# MODULIQ_TDC.net
KiCad netlist of a schematic drawn in Altium Designer
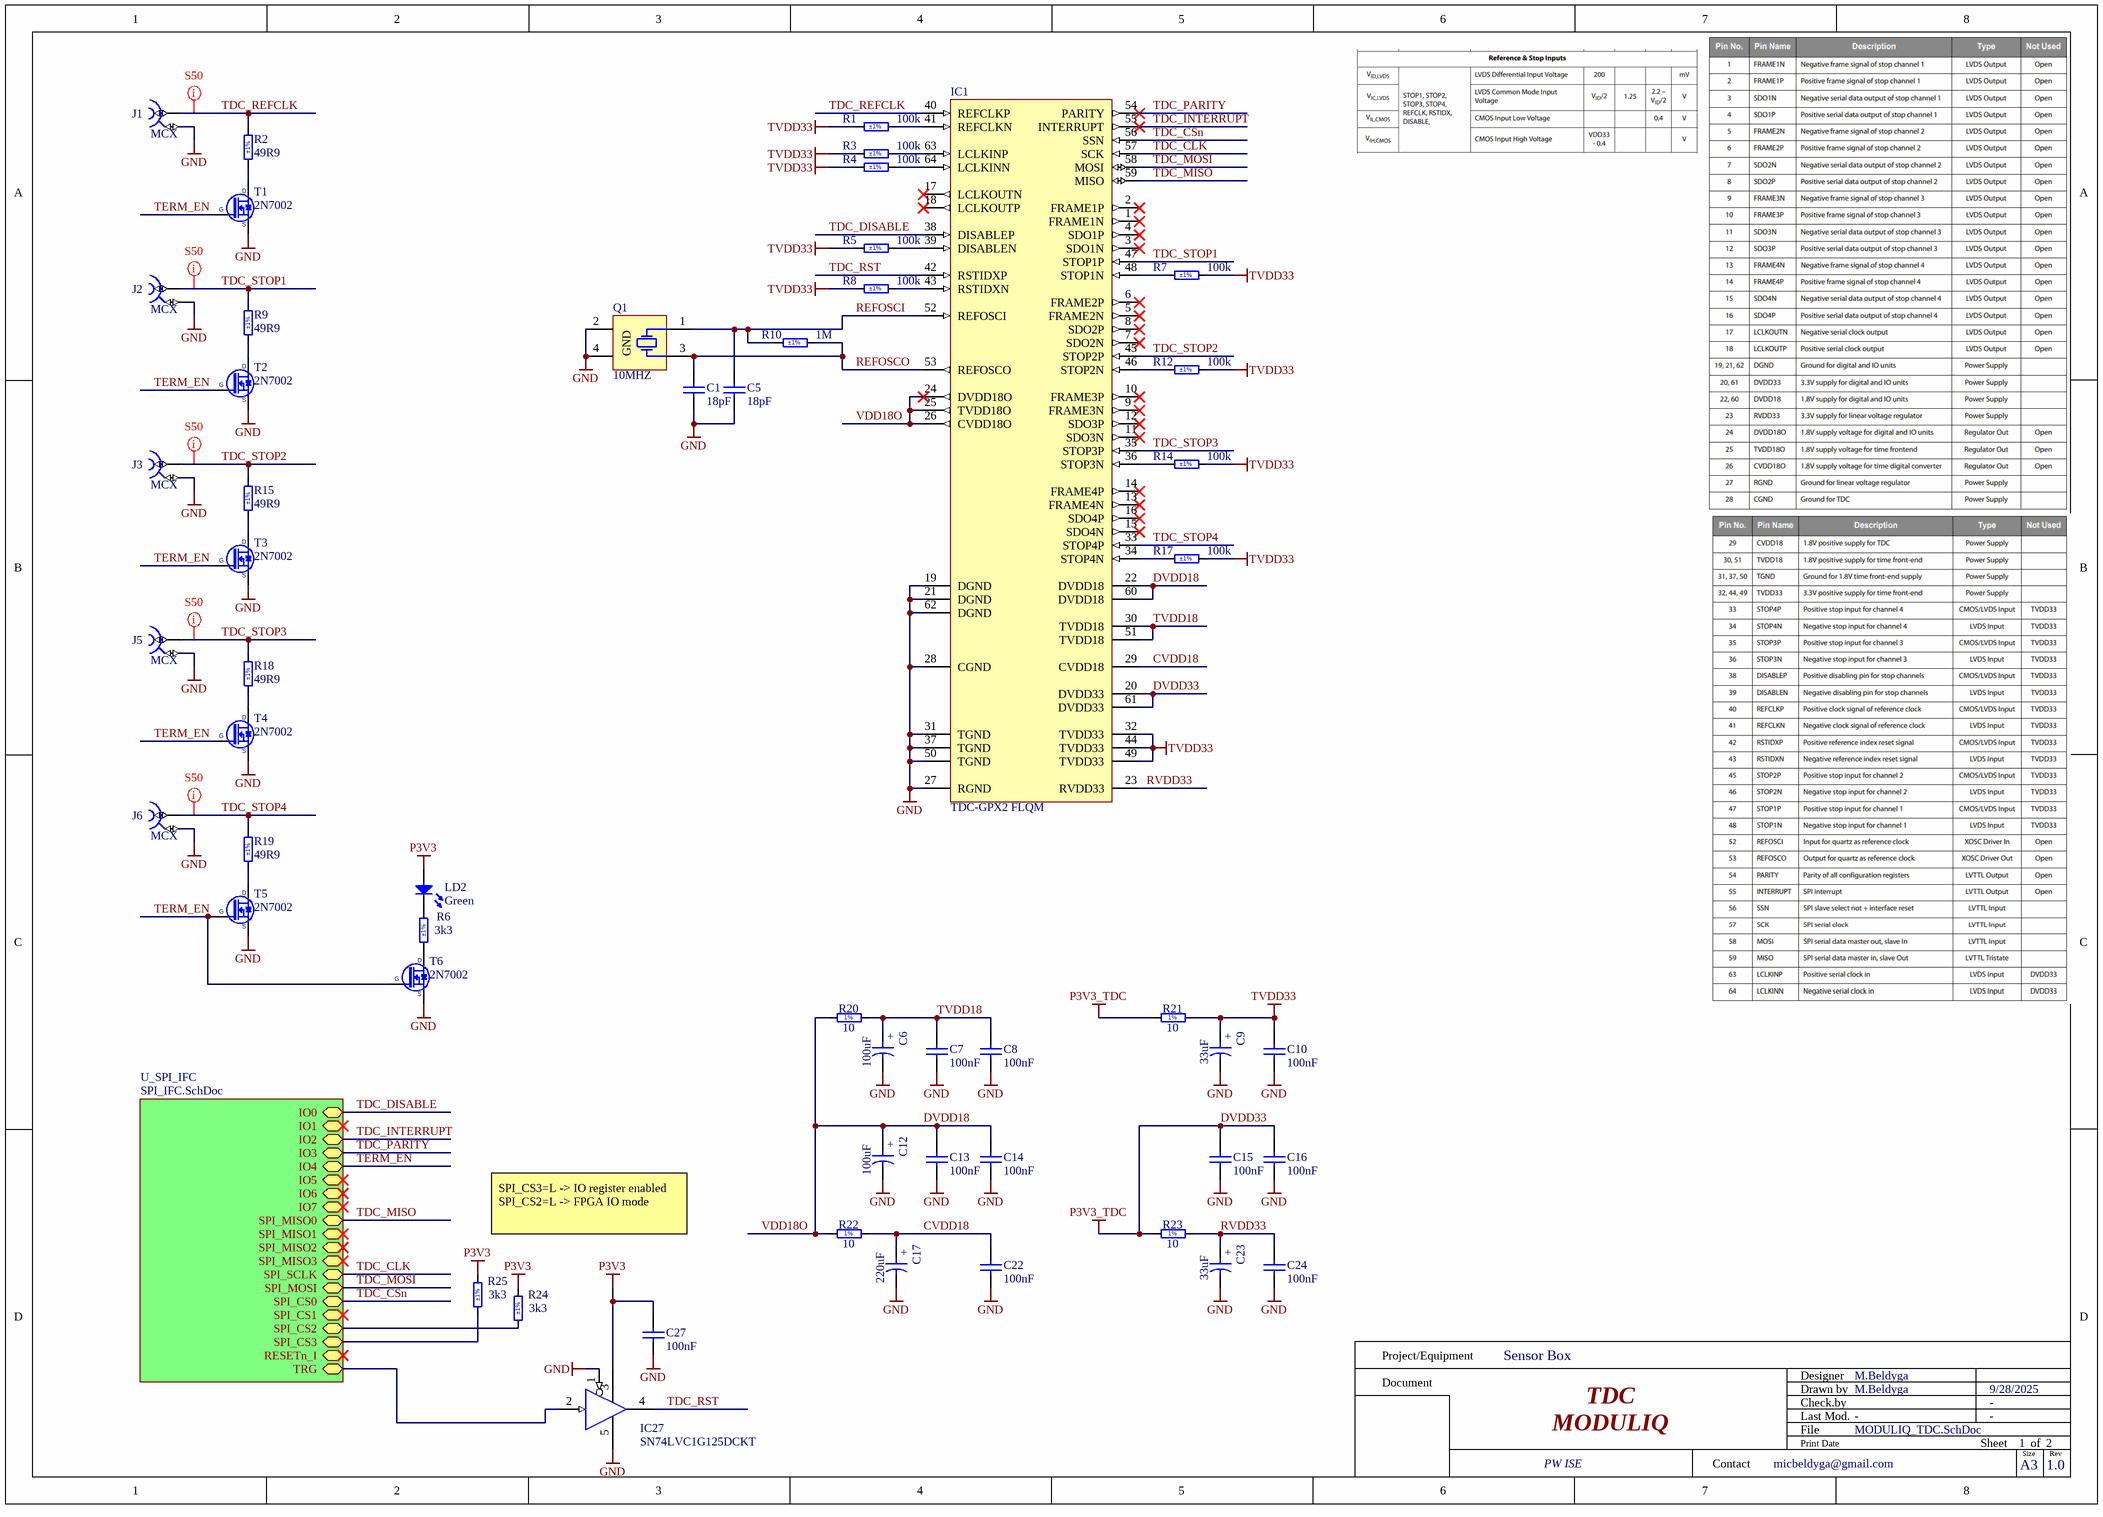
[diagram p0: MODULIQ_TDC.SchDoc]

(export (version "E")
  (design (tool "Eeschema 10.0.6"))
  (components
    (comp (ref "C1")
      (value "18pF")
      (footprint "CAPC1005X55N")
      (description "Non-polarised capacitor")
      (fields
        (field (name "PART NUMBER") "CC0402_18PF_50V_5%_C0G")
        (field (name "VOLTAGE") "50V")
        (field (name "AUTHOR") "CERN DEM JLC")
      )
      (libsource (lib "Capacitors") (part "Capacitor - non polarized"))
    )
    (comp (ref "C5")
      (value "18pF")
      (footprint "CAPC1005X55N")
      (description "Non-polarised capacitor")
      (fields
        (field (name "PART NUMBER") "CC0402_18PF_50V_5%_C0G")
        (field (name "VOLTAGE") "50V")
        (field (name "AUTHOR") "CERN DEM JLC")
      )
      (libsource (lib "Capacitors") (part "Capacitor - non polarized"))
    )
    (comp (ref "C6")
      (value "100uF")
      (footprint "CAPMP3216X180N")
      (description "Polarised capacitor")
      (fields
        (field (name "PART NUMBER") "CTE3216-18_100UF_6.3V_20%_ESR0500_AVX_TLJ")
        (field (name "VOLTAGE") "6.3V")
        (field (name "AUTHOR") "CERN DEM JLC")
      )
      (libsource (lib "Capacitors") (part "Capacitor - polarized"))
    )
    (comp (ref "C7")
      (value "100nF")
      (footprint "CAPC1005X55N")
      (description "Non-polarised capacitor")
      (fields
        (field (name "PART NUMBER") "CC0402_100NF_50V_10%_X7R")
        (field (name "VOLTAGE") "50V")
        (field (name "AUTHOR") "CERN DEM MR")
      )
      (libsource (lib "Capacitors") (part "Capacitor - non polarized"))
    )
    (comp (ref "C8")
      (value "100nF")
      (footprint "CAPC1005X55N")
      (description "Non-polarised capacitor")
      (fields
        (field (name "PART NUMBER") "CC0402_100NF_50V_10%_X7R")
        (field (name "VOLTAGE") "50V")
        (field (name "AUTHOR") "CERN DEM MR")
      )
      (libsource (lib "Capacitors") (part "Capacitor - non polarized"))
    )
    (comp (ref "C9")
      (value "33uF")
      (footprint "CAPMP3216X180N")
      (description "Polarised capacitor")
      (fields
        (field (name "PART NUMBER") "CTE3216-18_33UF_4V_10%")
        (field (name "VOLTAGE") "4V")
        (field (name "AUTHOR") "CERN DEM JLC")
      )
      (libsource (lib "Capacitors") (part "Capacitor - polarized"))
    )
    (comp (ref "C10")
      (value "100nF")
      (footprint "CAPC1005X55N")
      (description "Non-polarised capacitor")
      (fields
        (field (name "PART NUMBER") "CC0402_100NF_50V_10%_X7R")
        (field (name "VOLTAGE") "50V")
        (field (name "AUTHOR") "CERN DEM MR")
      )
      (libsource (lib "Capacitors") (part "Capacitor - non polarized"))
    )
    (comp (ref "C12")
      (value "100uF")
      (footprint "CAPMP3216X180N")
      (description "Polarised capacitor")
      (fields
        (field (name "PART NUMBER") "CTE3216-18_100UF_6.3V_20%_ESR0500_AVX_TLJ")
        (field (name "VOLTAGE") "6.3V")
        (field (name "AUTHOR") "CERN DEM JLC")
      )
      (libsource (lib "Capacitors") (part "Capacitor - polarized"))
    )
    (comp (ref "C13")
      (value "100nF")
      (footprint "CAPC1005X55N")
      (description "Non-polarised capacitor")
      (fields
        (field (name "PART NUMBER") "CC0402_100NF_50V_10%_X7R")
        (field (name "VOLTAGE") "50V")
        (field (name "AUTHOR") "CERN DEM MR")
      )
      (libsource (lib "Capacitors") (part "Capacitor - non polarized"))
    )
    (comp (ref "C14")
      (value "100nF")
      (footprint "CAPC1005X55N")
      (description "Non-polarised capacitor")
      (fields
        (field (name "PART NUMBER") "CC0402_100NF_50V_10%_X7R")
        (field (name "VOLTAGE") "50V")
        (field (name "AUTHOR") "CERN DEM MR")
      )
      (libsource (lib "Capacitors") (part "Capacitor - non polarized"))
    )
    (comp (ref "C15")
      (value "100nF")
      (footprint "CAPC1005X55N")
      (description "Non-polarised capacitor")
      (fields
        (field (name "PART NUMBER") "CC0402_100NF_50V_10%_X7R")
        (field (name "VOLTAGE") "50V")
        (field (name "AUTHOR") "CERN DEM MR")
      )
      (libsource (lib "Capacitors") (part "Capacitor - non polarized"))
    )
    (comp (ref "C16")
      (value "100nF")
      (footprint "CAPC1005X55N")
      (description "Non-polarised capacitor")
      (fields
        (field (name "PART NUMBER") "CC0402_100NF_50V_10%_X7R")
        (field (name "VOLTAGE") "50V")
        (field (name "AUTHOR") "CERN DEM MR")
      )
      (libsource (lib "Capacitors") (part "Capacitor - non polarized"))
    )
    (comp (ref "C17")
      (value "220uF")
      (footprint "CAPMP3528X210N")
      (description "Polarised capacitor")
      (fields
        (field (name "PART NUMBER") "CTE3528-21_220UF_2.5V_10%")
        (field (name "VOLTAGE") "2.5V")
        (field (name "AUTHOR") "CERN DEM JLC")
      )
      (libsource (lib "Capacitors") (part "Capacitor - polarized"))
    )
    (comp (ref "C22")
      (value "100nF")
      (footprint "CAPC1005X55N")
      (description "Non-polarised capacitor")
      (fields
        (field (name "PART NUMBER") "CC0402_100NF_50V_10%_X7R")
        (field (name "VOLTAGE") "50V")
        (field (name "AUTHOR") "CERN DEM MR")
      )
      (libsource (lib "Capacitors") (part "Capacitor - non polarized"))
    )
    (comp (ref "C23")
      (value "33uF")
      (footprint "CAPMP3216X180N")
      (description "Polarised capacitor")
      (fields
        (field (name "PART NUMBER") "CTE3216-18_33UF_4V_10%")
        (field (name "VOLTAGE") "4V")
        (field (name "AUTHOR") "CERN DEM JLC")
      )
      (libsource (lib "Capacitors") (part "Capacitor - polarized"))
    )
    (comp (ref "C24")
      (value "100nF")
      (footprint "CAPC1005X55N")
      (description "Non-polarised capacitor")
      (fields
        (field (name "PART NUMBER") "CC0402_100NF_50V_10%_X7R")
        (field (name "VOLTAGE") "50V")
        (field (name "AUTHOR") "CERN DEM MR")
      )
      (libsource (lib "Capacitors") (part "Capacitor - non polarized"))
    )
    (comp (ref "C27")
      (value "100nF")
      (footprint "CAPC1005X55N")
      (description "Non-polarised capacitor")
      (fields
        (field (name "PART NUMBER") "CC0402_100NF_50V_10%_X7R")
        (field (name "VOLTAGE") "50V")
        (field (name "AUTHOR") "CERN DEM MR")
      )
      (libsource (lib "Capacitors") (part "Capacitor - non polarized"))
    )
    (comp (ref "IC1")
      (value "TDC-GPX2 FLQM")
      (footprint "QFP50P1200X1200X160-64N")
      (description "4 Channel Time to Digital Converter")
      (fields
        (field (name "PART NUMBER") "TDC-GPX2")
        (field (name "MANUFACTURER") "AMS")
        (field (name "AUTHOR") "CERN DEM MR")
      )
      (libsource (lib "ICs And Semiconductors") (part "TDC-GPX2"))
    )
    (comp (ref "IC27")
      (value "SN74LVC1G125DCKT")
      (footprint "SOT65P210X110-5N")
      (description "Single Bus Buffer Gate With 3-State Output")
      (fields (field (name "MANUFACTURER") "TEXAS INSTRUMENTS") (field (name "AUTHOR") "CERN DEM JLC"))
      (libsource (lib "mb") (part "741G125"))
    )
    (comp (ref "J1")
      (value "MCX")
      (footprint "AMPHENOL_919-109J-51PX")
      (fields
        (field (name "PART NUMBER") "AMPHENOL_919-109J-51PX")
        (field (name "MANUFACTURER") "AMPHENOL")
        (field (name "MANUFACTURER PART NUMBER") "919-109J-51PX (MCX6251B1-3GT30G-50)")
        (field (name "AUTHOR") "CERN DEM BC")
      )
      (libsource (lib "Connectors") (part "Coax_1Female_1Shield"))
    )
    (comp (ref "J2")
      (value "MCX")
      (footprint "AMPHENOL_919-109J-51PX")
      (fields
        (field (name "PART NUMBER") "AMPHENOL_919-109J-51PX")
        (field (name "MANUFACTURER") "AMPHENOL")
        (field (name "MANUFACTURER PART NUMBER") "919-109J-51PX (MCX6251B1-3GT30G-50)")
        (field (name "AUTHOR") "CERN DEM BC")
      )
      (libsource (lib "Connectors") (part "Coax_1Female_1Shield"))
    )
    (comp (ref "J3")
      (value "MCX")
      (footprint "AMPHENOL_919-109J-51PX")
      (fields
        (field (name "PART NUMBER") "AMPHENOL_919-109J-51PX")
        (field (name "MANUFACTURER") "AMPHENOL")
        (field (name "MANUFACTURER PART NUMBER") "919-109J-51PX (MCX6251B1-3GT30G-50)")
        (field (name "AUTHOR") "CERN DEM BC")
      )
      (libsource (lib "Connectors") (part "Coax_1Female_1Shield"))
    )
    (comp (ref "J5")
      (value "MCX")
      (footprint "AMPHENOL_919-109J-51PX")
      (fields
        (field (name "PART NUMBER") "AMPHENOL_919-109J-51PX")
        (field (name "MANUFACTURER") "AMPHENOL")
        (field (name "MANUFACTURER PART NUMBER") "919-109J-51PX (MCX6251B1-3GT30G-50)")
        (field (name "AUTHOR") "CERN DEM BC")
      )
      (libsource (lib "Connectors") (part "Coax_1Female_1Shield"))
    )
    (comp (ref "J6")
      (value "MCX")
      (footprint "AMPHENOL_919-109J-51PX")
      (fields
        (field (name "PART NUMBER") "AMPHENOL_919-109J-51PX")
        (field (name "MANUFACTURER") "AMPHENOL")
        (field (name "MANUFACTURER PART NUMBER") "919-109J-51PX (MCX6251B1-3GT30G-50)")
        (field (name "AUTHOR") "CERN DEM BC")
      )
      (libsource (lib "Connectors") (part "Coax_1Female_1Shield"))
    )
    (comp (ref "LD2")
      (value "Green")
      (footprint "LED_KINGBRIGHT_KP-1608CGCK")
      (description "LED Green 1C 2A")
      (fields
        (field (name "PART NUMBER") "LED_KINGBRIGHT_KP-1608CGCK")
        (field (name "MANUFACTURER") "KINGBRIGHT")
        (field (name "AUTHOR") "CERN DEM HF")
      )
      (libsource (lib "ICs And Semiconductors") (part "LED Green 1C 2A"))
    )
    (comp (ref "Q1")
      (value "10MHZ")
      (footprint "XTAL_ABRACON_ABMM2")
      (description "Crystal 4 pins 1=XTAL Control 2=GND3=XTAL 4=GND")
      (fields
        (field (name "PART NUMBER") "XTAL_10MHZ_ABRACON_ABMM2-10.000MHZ-E2-T")
        (field (name "MANUFACTURER") "ABRACON")
        (field (name "AUTHOR") "CERN DEM MR")
      )
      (libsource (lib "ICs And Semiconductors") (part "Quartz Crystal 1X 2GND 3X 4GND"))
    )
    (comp (ref "R1")
      (value "100k")
      (footprint "RESC1005X40N")
      (description "Resistor - 1%")
      (fields
        (field (name "TOLERANCE") "±1%")
        (field (name "PART NUMBER") "R0402_100K_1%_0.0625W_100PPM")
        (field (name "POWER") "0.0625W")
        (field (name "AUTHOR") "CERN DEM JLC")
      )
      (libsource (lib "Resistors") (part "Resistor - 1%"))
    )
    (comp (ref "R2")
      (value "49R9")
      (footprint "RESC3225X70N")
      (description "Resistor - 1%")
      (fields
        (field (name "TOLERANCE") "±1%")
        (field (name "PART NUMBER") "R1210_49R9_1%_0.5W_100PPM_VISHAY_CRCW")
        (field (name "POWER") "0.5W")
        (field (name "AUTHOR") "CERN DEM JMW")
      )
      (libsource (lib "Resistors") (part "Resistor - 1%"))
    )
    (comp (ref "R3")
      (value "100k")
      (footprint "RESC1005X40N")
      (description "Resistor - 1%")
      (fields
        (field (name "TOLERANCE") "±1%")
        (field (name "PART NUMBER") "R0402_100K_1%_0.0625W_100PPM")
        (field (name "POWER") "0.0625W")
        (field (name "AUTHOR") "CERN DEM JLC")
      )
      (libsource (lib "Resistors") (part "Resistor - 1%"))
    )
    (comp (ref "R4")
      (value "100k")
      (footprint "RESC1005X40N")
      (description "Resistor - 1%")
      (fields
        (field (name "TOLERANCE") "±1%")
        (field (name "PART NUMBER") "R0402_100K_1%_0.0625W_100PPM")
        (field (name "POWER") "0.0625W")
        (field (name "AUTHOR") "CERN DEM JLC")
      )
      (libsource (lib "Resistors") (part "Resistor - 1%"))
    )
    (comp (ref "R5")
      (value "100k")
      (footprint "RESC1005X40N")
      (description "Resistor - 1%")
      (fields
        (field (name "TOLERANCE") "±1%")
        (field (name "PART NUMBER") "R0402_100K_1%_0.0625W_100PPM")
        (field (name "POWER") "0.0625W")
        (field (name "AUTHOR") "CERN DEM JLC")
      )
      (libsource (lib "Resistors") (part "Resistor - 1%"))
    )
    (comp (ref "R6")
      (value "3k3")
      (footprint "RESC1005X40N")
      (description "Resistor - 1%")
      (fields
        (field (name "TOLERANCE") "±1%")
        (field (name "PART NUMBER") "R0402_3K3_1%_0.0625W_100PPM")
        (field (name "POWER") "0.0625W")
        (field (name "AUTHOR") "CERN DEM JLC")
      )
      (libsource (lib "Resistors") (part "Resistor - 1%"))
    )
    (comp (ref "R7")
      (value "100k")
      (footprint "RESC1005X40N")
      (description "Resistor - 1%")
      (fields
        (field (name "TOLERANCE") "±1%")
        (field (name "PART NUMBER") "R0402_100K_1%_0.0625W_100PPM")
        (field (name "POWER") "0.0625W")
        (field (name "AUTHOR") "CERN DEM JLC")
      )
      (libsource (lib "Resistors") (part "Resistor - 1%"))
    )
    (comp (ref "R8")
      (value "100k")
      (footprint "RESC1005X40N")
      (description "Resistor - 1%")
      (fields
        (field (name "TOLERANCE") "±1%")
        (field (name "PART NUMBER") "R0402_100K_1%_0.0625W_100PPM")
        (field (name "POWER") "0.0625W")
        (field (name "AUTHOR") "CERN DEM JLC")
      )
      (libsource (lib "Resistors") (part "Resistor - 1%"))
    )
    (comp (ref "R9")
      (value "49R9")
      (footprint "RESC3225X70N")
      (description "Resistor - 1%")
      (fields
        (field (name "TOLERANCE") "±1%")
        (field (name "PART NUMBER") "R1210_49R9_1%_0.5W_100PPM_VISHAY_CRCW")
        (field (name "POWER") "0.5W")
        (field (name "AUTHOR") "CERN DEM JMW")
      )
      (libsource (lib "Resistors") (part "Resistor - 1%"))
    )
    (comp (ref "R10")
      (value "1M")
      (footprint "RESC1005X40N")
      (description "Resistor - 1%")
      (fields
        (field (name "TOLERANCE") "±1%")
        (field (name "PART NUMBER") "R0402_1M_1%_0.0625W_100PPM")
        (field (name "POWER") "0.0625W")
        (field (name "AUTHOR") "CERN DEM JLC")
      )
      (libsource (lib "Resistors") (part "Resistor - 1%"))
    )
    (comp (ref "R12")
      (value "100k")
      (footprint "RESC1005X40N")
      (description "Resistor - 1%")
      (fields
        (field (name "TOLERANCE") "±1%")
        (field (name "PART NUMBER") "R0402_100K_1%_0.0625W_100PPM")
        (field (name "POWER") "0.0625W")
        (field (name "AUTHOR") "CERN DEM JLC")
      )
      (libsource (lib "Resistors") (part "Resistor - 1%"))
    )
    (comp (ref "R14")
      (value "100k")
      (footprint "RESC1005X40N")
      (description "Resistor - 1%")
      (fields
        (field (name "TOLERANCE") "±1%")
        (field (name "PART NUMBER") "R0402_100K_1%_0.0625W_100PPM")
        (field (name "POWER") "0.0625W")
        (field (name "AUTHOR") "CERN DEM JLC")
      )
      (libsource (lib "Resistors") (part "Resistor - 1%"))
    )
    (comp (ref "R15")
      (value "49R9")
      (footprint "RESC3225X70N")
      (description "Resistor - 1%")
      (fields
        (field (name "TOLERANCE") "±1%")
        (field (name "PART NUMBER") "R1210_49R9_1%_0.5W_100PPM_VISHAY_CRCW")
        (field (name "POWER") "0.5W")
        (field (name "AUTHOR") "CERN DEM JMW")
      )
      (libsource (lib "Resistors") (part "Resistor - 1%"))
    )
    (comp (ref "R17")
      (value "100k")
      (footprint "RESC1005X40N")
      (description "Resistor - 1%")
      (fields
        (field (name "TOLERANCE") "±1%")
        (field (name "PART NUMBER") "R0402_100K_1%_0.0625W_100PPM")
        (field (name "POWER") "0.0625W")
        (field (name "AUTHOR") "CERN DEM JLC")
      )
      (libsource (lib "Resistors") (part "Resistor - 1%"))
    )
    (comp (ref "R18")
      (value "49R9")
      (footprint "RESC3225X70N")
      (description "Resistor - 1%")
      (fields
        (field (name "TOLERANCE") "±1%")
        (field (name "PART NUMBER") "R1210_49R9_1%_0.5W_100PPM_VISHAY_CRCW")
        (field (name "POWER") "0.5W")
        (field (name "AUTHOR") "CERN DEM JMW")
      )
      (libsource (lib "Resistors") (part "Resistor - 1%"))
    )
    (comp (ref "R19")
      (value "49R9")
      (footprint "RESC3225X70N")
      (description "Resistor - 1%")
      (fields
        (field (name "TOLERANCE") "±1%")
        (field (name "PART NUMBER") "R1210_49R9_1%_0.5W_100PPM_VISHAY_CRCW")
        (field (name "POWER") "0.5W")
        (field (name "AUTHOR") "CERN DEM JMW")
      )
      (libsource (lib "Resistors") (part "Resistor - 1%"))
    )
    (comp (ref "R20")
      (value "10")
      (footprint "RESC1005X40N")
      (description "Resistor - 1%")
      (fields
        (field (name "PART NUMBER") "R0402_10R_1%_0.0625W_200PPM")
        (field (name "POWER") "0.0625W")
        (field (name "AUTHOR") "CERN DEM JLC")
      )
      (libsource (lib "Resistors") (part "Resistor - 1%"))
    )
    (comp (ref "R21")
      (value "10")
      (footprint "RESC1005X40N")
      (description "Resistor - 1%")
      (fields
        (field (name "PART NUMBER") "R0402_10R_1%_0.0625W_200PPM")
        (field (name "POWER") "0.0625W")
        (field (name "AUTHOR") "CERN DEM JLC")
      )
      (libsource (lib "Resistors") (part "Resistor - 1%"))
    )
    (comp (ref "R22")
      (value "10")
      (footprint "RESC1005X40N")
      (description "Resistor - 1%")
      (fields
        (field (name "PART NUMBER") "R0402_10R_1%_0.0625W_200PPM")
        (field (name "POWER") "0.0625W")
        (field (name "AUTHOR") "CERN DEM JLC")
      )
      (libsource (lib "Resistors") (part "Resistor - 1%"))
    )
    (comp (ref "R23")
      (value "10")
      (footprint "RESC1005X40N")
      (description "Resistor - 1%")
      (fields
        (field (name "PART NUMBER") "R0402_10R_1%_0.0625W_200PPM")
        (field (name "POWER") "0.0625W")
        (field (name "AUTHOR") "CERN DEM JLC")
      )
      (libsource (lib "Resistors") (part "Resistor - 1%"))
    )
    (comp (ref "R24")
      (value "3k3")
      (footprint "RESC1005X40N")
      (description "Resistor - 1%")
      (fields
        (field (name "TOLERANCE") "±1%")
        (field (name "PART NUMBER") "R0402_3K3_1%_0.0625W_100PPM")
        (field (name "POWER") "0.0625W")
        (field (name "AUTHOR") "CERN DEM JLC")
      )
      (libsource (lib "Resistors") (part "Resistor - 1%"))
    )
    (comp (ref "R25")
      (value "3k3")
      (footprint "RESC1005X40N")
      (description "Resistor - 1%")
      (fields
        (field (name "TOLERANCE") "±1%")
        (field (name "PART NUMBER") "R0402_3K3_1%_0.0625W_100PPM")
        (field (name "POWER") "0.0625W")
        (field (name "AUTHOR") "CERN DEM JLC")
      )
      (libsource (lib "Resistors") (part "Resistor - 1%"))
    )
    (comp (ref "T1")
      (value "2N7002")
      (footprint "SOT95P240X130-3N")
      (description "N-CHANNEL MOSFET WITH DIODE")
      (fields (field (name "MANUFACTURER") "FAIRCHILD SEMICONDUCTOR") (field (name "AUTHOR") "CERN DEM JLC"))
      (libsource (lib "ICs And Semiconductors") (part "N-MOSFET-D 1G 2S 3D"))
    )
    (comp (ref "T2")
      (value "2N7002")
      (footprint "SOT95P240X130-3N")
      (description "N-CHANNEL MOSFET WITH DIODE")
      (fields (field (name "MANUFACTURER") "FAIRCHILD SEMICONDUCTOR") (field (name "AUTHOR") "CERN DEM JLC"))
      (libsource (lib "ICs And Semiconductors") (part "N-MOSFET-D 1G 2S 3D"))
    )
    (comp (ref "T3")
      (value "2N7002")
      (footprint "SOT95P240X130-3N")
      (description "N-CHANNEL MOSFET WITH DIODE")
      (fields (field (name "MANUFACTURER") "FAIRCHILD SEMICONDUCTOR") (field (name "AUTHOR") "CERN DEM JLC"))
      (libsource (lib "ICs And Semiconductors") (part "N-MOSFET-D 1G 2S 3D"))
    )
    (comp (ref "T4")
      (value "2N7002")
      (footprint "SOT95P240X130-3N")
      (description "N-CHANNEL MOSFET WITH DIODE")
      (fields (field (name "MANUFACTURER") "FAIRCHILD SEMICONDUCTOR") (field (name "AUTHOR") "CERN DEM JLC"))
      (libsource (lib "ICs And Semiconductors") (part "N-MOSFET-D 1G 2S 3D"))
    )
    (comp (ref "T5")
      (value "2N7002")
      (footprint "SOT95P240X130-3N")
      (description "N-CHANNEL MOSFET WITH DIODE")
      (fields (field (name "MANUFACTURER") "FAIRCHILD SEMICONDUCTOR") (field (name "AUTHOR") "CERN DEM JLC"))
      (libsource (lib "ICs And Semiconductors") (part "N-MOSFET-D 1G 2S 3D"))
    )
    (comp (ref "T6")
      (value "2N7002")
      (footprint "SOT95P240X130-3N")
      (description "N-CHANNEL MOSFET WITH DIODE")
      (fields (field (name "MANUFACTURER") "FAIRCHILD SEMICONDUCTOR") (field (name "AUTHOR") "CERN DEM JLC"))
      (libsource (lib "ICs And Semiconductors") (part "N-MOSFET-D 1G 2S 3D"))
    )
  )
  (nets
    (net (code "1") (name "/CVDD18") (class "Default")
      (node (ref "C17") (pin "1") (pinfunction "1_1") (pintype "passive"))
      (node (ref "C22") (pin "2") (pinfunction "2_2") (pintype "passive"))
      (node (ref "IC1") (pin "29") (pinfunction "CVDD18_29") (pintype "power_in"))
      (node (ref "R22") (pin "2") (pinfunction "2_2") (pintype "passive"))
    )
    (net (code "2") (name "/DVDD18") (class "Default")
      (node (ref "C12") (pin "1") (pinfunction "1_1") (pintype "passive"))
      (node (ref "C13") (pin "2") (pinfunction "2_2") (pintype "passive"))
      (node (ref "C14") (pin "2") (pinfunction "2_2") (pintype "passive"))
      (node (ref "IC1") (pin "22") (pinfunction "DVDD18_22") (pintype "power_in"))
      (node (ref "IC1") (pin "24") (pinfunction "DVDD18O_24") (pintype "output"))
      (node (ref "IC1") (pin "25") (pinfunction "TVDD18O_25") (pintype "output"))
      (node (ref "IC1") (pin "26") (pinfunction "CVDD18O_26") (pintype "output"))
      (node (ref "IC1") (pin "60") (pinfunction "DVDD18_60") (pintype "power_in"))
      (node (ref "R20") (pin "1") (pinfunction "1_1") (pintype "passive"))
      (node (ref "R22") (pin "1") (pinfunction "1_1") (pintype "passive"))
    )
    (net (code "7") (name "/REFOSCI") (class "Default")
      (node (ref "C5") (pin "2") (pinfunction "2_2") (pintype "passive"))
      (node (ref "IC1") (pin "52") (pinfunction "REFOSCI_52") (pintype "input"))
      (node (ref "Q1") (pin "1") (pinfunction "X_1") (pintype "passive"))
      (node (ref "R10") (pin "2") (pinfunction "2_2") (pintype "passive"))
    )
    (net (code "8") (name "/REFOSCO") (class "Default")
      (node (ref "C1") (pin "2") (pinfunction "2_2") (pintype "passive"))
      (node (ref "IC1") (pin "53") (pinfunction "REFOSCO_53") (pintype "output"))
      (node (ref "Q1") (pin "3") (pinfunction "X_3") (pintype "passive"))
      (node (ref "R10") (pin "1") (pinfunction "1_1") (pintype "passive"))
    )
    (net (code "10") (name "/RVDD33") (class "Default")
      (node (ref "C23") (pin "1") (pinfunction "1_1") (pintype "passive"))
      (node (ref "C24") (pin "2") (pinfunction "2_2") (pintype "passive"))
      (node (ref "IC1") (pin "23") (pinfunction "RVDD33_23") (pintype "power_in"))
      (node (ref "R23") (pin "2") (pinfunction "2_2") (pintype "passive"))
    )
    (net (code "12") (name "/SPI_CS2") (class "Default")
      (node (ref "R24") (pin "2") (pinfunction "2_2") (pintype "passive"))
    )
    (net (code "13") (name "/SPI_CS3") (class "Default")
      (node (ref "R25") (pin "2") (pinfunction "2_2") (pintype "passive"))
    )
    (net (code "17") (name "/TDC_CLK") (class "Default")
      (node (ref "IC1") (pin "57") (pinfunction "SCK_57") (pintype "input"))
    )
    (net (code "18") (name "/TDC_CSn") (class "Default")
      (node (ref "IC1") (pin "56") (pinfunction "SSN_56") (pintype "input"))
    )
    (net (code "19") (name "/TDC_DISABLE") (class "Default")
      (node (ref "IC1") (pin "38") (pinfunction "DISABLEP_38") (pintype "input"))
    )
    (net (code "20") (name "/TDC_INTERRUPT") (class "Default")
      (node (ref "IC1") (pin "55") (pinfunction "INTERRUPT_55") (pintype "output+no_connect"))
    )
    (net (code "21") (name "/TDC_MISO") (class "Default")
      (node (ref "IC1") (pin "59") (pinfunction "MISO_59") (pintype "bidirectional"))
    )
    (net (code "22") (name "/TDC_MOSI") (class "Default")
      (node (ref "IC1") (pin "58") (pinfunction "MOSI_58") (pintype "bidirectional"))
    )
    (net (code "23") (name "/TDC_PARITY") (class "Default")
      (node (ref "IC1") (pin "54") (pinfunction "PARITY_54") (pintype "output+no_connect"))
    )
    (net (code "24") (name "/TDC_REFCLK") (class "Default")
      (node (ref "IC1") (pin "40") (pinfunction "REFCLKP_40") (pintype "input"))
      (node (ref "J1") (pin "1") (pinfunction "1_1") (pintype "bidirectional"))
      (node (ref "R2") (pin "2") (pinfunction "2_2") (pintype "passive"))
    )
    (net (code "25") (name "/TDC_RST") (class "Default")
      (node (ref "IC1") (pin "42") (pinfunction "RSTIDXP_42") (pintype "input"))
      (node (ref "IC27") (pin "4") (pinfunction "OUT_4") (pintype "tri_state"))
    )
    (net (code "26") (name "/TDC_STOP1") (class "Default")
      (node (ref "IC1") (pin "47") (pinfunction "STOP1P_47") (pintype "input"))
      (node (ref "J2") (pin "1") (pinfunction "1_1") (pintype "bidirectional"))
      (node (ref "R9") (pin "2") (pinfunction "2_2") (pintype "passive"))
    )
    (net (code "27") (name "/TDC_STOP2") (class "Default")
      (node (ref "IC1") (pin "45") (pinfunction "STOP2P_45") (pintype "input"))
      (node (ref "J3") (pin "1") (pinfunction "1_1") (pintype "bidirectional"))
      (node (ref "R15") (pin "2") (pinfunction "2_2") (pintype "passive"))
    )
    (net (code "28") (name "/TDC_STOP3") (class "Default")
      (node (ref "IC1") (pin "35") (pinfunction "STOP3P_35") (pintype "input"))
      (node (ref "J5") (pin "1") (pinfunction "1_1") (pintype "bidirectional"))
      (node (ref "R18") (pin "2") (pinfunction "2_2") (pintype "passive"))
    )
    (net (code "29") (name "/TDC_STOP4") (class "Default")
      (node (ref "IC1") (pin "33") (pinfunction "STOP4P_33") (pintype "input"))
      (node (ref "J6") (pin "1") (pinfunction "1_1") (pintype "bidirectional"))
      (node (ref "R19") (pin "2") (pinfunction "2_2") (pintype "passive"))
    )
    (net (code "30") (name "/TERM_EN") (class "Default")
      (node (ref "T1") (pin "1") (pinfunction "G_1") (pintype "passive"))
      (node (ref "T2") (pin "1") (pinfunction "G_1") (pintype "passive"))
      (node (ref "T3") (pin "1") (pinfunction "G_1") (pintype "passive"))
      (node (ref "T4") (pin "1") (pinfunction "G_1") (pintype "passive"))
      (node (ref "T5") (pin "1") (pinfunction "G_1") (pintype "passive"))
      (node (ref "T6") (pin "1") (pinfunction "G_1") (pintype "passive"))
    )
    (net (code "31") (name "/TRG") (class "Default")
      (node (ref "IC27") (pin "2") (pinfunction "IN_2") (pintype "input"))
    )
    (net (code "32") (name "/TVDD18") (class "Default")
      (node (ref "C6") (pin "1") (pinfunction "1_1") (pintype "passive"))
      (node (ref "C7") (pin "2") (pinfunction "2_2") (pintype "passive"))
      (node (ref "C8") (pin "2") (pinfunction "2_2") (pintype "passive"))
      (node (ref "IC1") (pin "30") (pinfunction "TVDD18_30") (pintype "power_in"))
      (node (ref "IC1") (pin "51") (pinfunction "TVDD18_51") (pintype "power_in"))
      (node (ref "R20") (pin "2") (pinfunction "2_2") (pintype "passive"))
    )
    (net (code "33") (name "GND") (class "Default")
      (node (ref "C1") (pin "1") (pinfunction "1_1") (pintype "passive"))
      (node (ref "C10") (pin "1") (pinfunction "1_1") (pintype "passive"))
      (node (ref "C12") (pin "2") (pinfunction "2_2") (pintype "passive"))
      (node (ref "C13") (pin "1") (pinfunction "1_1") (pintype "passive"))
      (node (ref "C14") (pin "1") (pinfunction "1_1") (pintype "passive"))
      (node (ref "C15") (pin "1") (pinfunction "1_1") (pintype "passive"))
      (node (ref "C16") (pin "1") (pinfunction "1_1") (pintype "passive"))
      (node (ref "C17") (pin "2") (pinfunction "2_2") (pintype "passive"))
      (node (ref "C22") (pin "1") (pinfunction "1_1") (pintype "passive"))
      (node (ref "C23") (pin "2") (pinfunction "2_2") (pintype "passive"))
      (node (ref "C24") (pin "1") (pinfunction "1_1") (pintype "passive"))
      (node (ref "C27") (pin "1") (pinfunction "1_1") (pintype "passive"))
      (node (ref "C5") (pin "1") (pinfunction "1_1") (pintype "passive"))
      (node (ref "C6") (pin "2") (pinfunction "2_2") (pintype "passive"))
      (node (ref "C7") (pin "1") (pinfunction "1_1") (pintype "passive"))
      (node (ref "C8") (pin "1") (pinfunction "1_1") (pintype "passive"))
      (node (ref "C9") (pin "2") (pinfunction "2_2") (pintype "passive"))
      (node (ref "IC1") (pin "19") (pinfunction "DGND_19") (pintype "power_in"))
      (node (ref "IC1") (pin "21") (pinfunction "DGND_21") (pintype "power_in"))
      (node (ref "IC1") (pin "27") (pinfunction "RGND_27") (pintype "power_in"))
      (node (ref "IC1") (pin "28") (pinfunction "CGND_28") (pintype "power_in"))
      (node (ref "IC1") (pin "31") (pinfunction "TGND_31") (pintype "power_in"))
      (node (ref "IC1") (pin "37") (pinfunction "TGND_37") (pintype "power_in"))
      (node (ref "IC1") (pin "50") (pinfunction "TGND_50") (pintype "power_in"))
      (node (ref "IC1") (pin "62") (pinfunction "DGND_62") (pintype "power_in"))
      (node (ref "IC27") (pin "1") (pinfunction "~{G}_1") (pintype "input"))
      (node (ref "IC27") (pin "5") (pinfunction "VCC_5") (pintype "power_in"))
      (node (ref "J1") (pin "2") (pinfunction "2_2") (pintype "bidirectional"))
      (node (ref "J2") (pin "2") (pinfunction "2_2") (pintype "bidirectional"))
      (node (ref "J3") (pin "2") (pinfunction "2_2") (pintype "bidirectional"))
      (node (ref "J5") (pin "2") (pinfunction "2_2") (pintype "bidirectional"))
      (node (ref "J6") (pin "2") (pinfunction "2_2") (pintype "bidirectional"))
      (node (ref "Q1") (pin "2") (pinfunction "GND_2") (pintype "power_in"))
      (node (ref "Q1") (pin "4") (pinfunction "GND_4") (pintype "power_in"))
      (node (ref "T1") (pin "2") (pinfunction "S_2") (pintype "passive"))
      (node (ref "T2") (pin "2") (pinfunction "S_2") (pintype "passive"))
      (node (ref "T3") (pin "2") (pinfunction "S_2") (pintype "passive"))
      (node (ref "T4") (pin "2") (pinfunction "S_2") (pintype "passive"))
      (node (ref "T5") (pin "2") (pinfunction "S_2") (pintype "passive"))
      (node (ref "T6") (pin "2") (pinfunction "S_2") (pintype "passive"))
    )
    (net (code "34") (name "Net-(IC1-DISABLEN)") (class "Default")
      (node (ref "IC1") (pin "39") (pinfunction "DISABLEN_39") (pintype "input"))
      (node (ref "R5") (pin "1") (pinfunction "1_1") (pintype "passive"))
    )
    (net (code "35") (name "Net-(IC1-LCLKINN)") (class "Default")
      (node (ref "IC1") (pin "64") (pinfunction "LCLKINN_64") (pintype "input"))
      (node (ref "R4") (pin "1") (pinfunction "1_1") (pintype "passive"))
    )
    (net (code "36") (name "Net-(IC1-LCLKINP)") (class "Default")
      (node (ref "IC1") (pin "63") (pinfunction "LCLKINP_63") (pintype "input"))
      (node (ref "R3") (pin "1") (pinfunction "1_1") (pintype "passive"))
    )
    (net (code "37") (name "Net-(IC1-REFCLKN)") (class "Default")
      (node (ref "IC1") (pin "41") (pinfunction "REFCLKN_41") (pintype "input"))
      (node (ref "R1") (pin "1") (pinfunction "1_1") (pintype "passive"))
    )
    (net (code "38") (name "Net-(IC1-RSTIDXN)") (class "Default")
      (node (ref "IC1") (pin "43") (pinfunction "RSTIDXN_43") (pintype "input"))
      (node (ref "R8") (pin "1") (pinfunction "1_1") (pintype "passive"))
    )
    (net (code "39") (name "Net-(IC1-STOP1N)") (class "Default")
      (node (ref "IC1") (pin "48") (pinfunction "STOP1N_48") (pintype "input"))
      (node (ref "R7") (pin "1") (pinfunction "1_1") (pintype "passive"))
    )
    (net (code "40") (name "Net-(IC1-STOP2N)") (class "Default")
      (node (ref "IC1") (pin "46") (pinfunction "STOP2N_46") (pintype "input"))
      (node (ref "R12") (pin "1") (pinfunction "1_1") (pintype "passive"))
    )
    (net (code "41") (name "Net-(IC1-STOP3N)") (class "Default")
      (node (ref "IC1") (pin "36") (pinfunction "STOP3N_36") (pintype "input"))
      (node (ref "R14") (pin "1") (pinfunction "1_1") (pintype "passive"))
    )
    (net (code "42") (name "Net-(IC1-STOP4N)") (class "Default")
      (node (ref "IC1") (pin "34") (pinfunction "STOP4N_34") (pintype "input"))
      (node (ref "R17") (pin "1") (pinfunction "1_1") (pintype "passive"))
    )
    (net (code "43") (name "Net-(LD2-C)") (class "Default")
      (node (ref "LD2") (pin "1") (pinfunction "C_1") (pintype "passive"))
      (node (ref "R6") (pin "1") (pinfunction "1_1") (pintype "passive"))
    )
    (net (code "44") (name "Net-(T1-D)") (class "Default")
      (node (ref "R2") (pin "1") (pinfunction "1_1") (pintype "passive"))
      (node (ref "T1") (pin "3") (pinfunction "D_3") (pintype "passive"))
    )
    (net (code "45") (name "Net-(T2-D)") (class "Default")
      (node (ref "R9") (pin "1") (pinfunction "1_1") (pintype "passive"))
      (node (ref "T2") (pin "3") (pinfunction "D_3") (pintype "passive"))
    )
    (net (code "46") (name "Net-(T3-D)") (class "Default")
      (node (ref "R15") (pin "1") (pinfunction "1_1") (pintype "passive"))
      (node (ref "T3") (pin "3") (pinfunction "D_3") (pintype "passive"))
    )
    (net (code "47") (name "Net-(T4-D)") (class "Default")
      (node (ref "R18") (pin "1") (pinfunction "1_1") (pintype "passive"))
      (node (ref "T4") (pin "3") (pinfunction "D_3") (pintype "passive"))
    )
    (net (code "48") (name "Net-(T5-D)") (class "Default")
      (node (ref "R19") (pin "1") (pinfunction "1_1") (pintype "passive"))
      (node (ref "T5") (pin "3") (pinfunction "D_3") (pintype "passive"))
    )
    (net (code "49") (name "Net-(T6-D)") (class "Default")
      (node (ref "R6") (pin "2") (pinfunction "2_2") (pintype "passive"))
      (node (ref "T6") (pin "3") (pinfunction "D_3") (pintype "passive"))
    )
    (net (code "50") (name "P3V3") (class "Default")
      (node (ref "C27") (pin "2") (pinfunction "2_2") (pintype "passive"))
      (node (ref "IC27") (pin "3") (pinfunction "GND_3") (pintype "power_in"))
      (node (ref "LD2") (pin "2") (pinfunction "A_2") (pintype "passive"))
      (node (ref "R24") (pin "1") (pinfunction "1_1") (pintype "passive"))
      (node (ref "R25") (pin "1") (pinfunction "1_1") (pintype "passive"))
    )
    (net (code "51") (name "P3V3_TDC") (class "Default")
      (node (ref "C15") (pin "2") (pinfunction "2_2") (pintype "passive"))
      (node (ref "C16") (pin "2") (pinfunction "2_2") (pintype "passive"))
      (node (ref "IC1") (pin "20") (pinfunction "DVDD33_20") (pintype "power_in"))
      (node (ref "IC1") (pin "61") (pinfunction "DVDD33_61") (pintype "power_in"))
      (node (ref "R21") (pin "1") (pinfunction "1_1") (pintype "passive"))
      (node (ref "R23") (pin "1") (pinfunction "1_1") (pintype "passive"))
    )
    (net (code "52") (name "TVDD33") (class "Default")
      (node (ref "C10") (pin "2") (pinfunction "2_2") (pintype "passive"))
      (node (ref "C9") (pin "1") (pinfunction "1_1") (pintype "passive"))
      (node (ref "IC1") (pin "32") (pinfunction "TVDD33_32") (pintype "power_in"))
      (node (ref "IC1") (pin "44") (pinfunction "TVDD33_44") (pintype "power_in"))
      (node (ref "IC1") (pin "49") (pinfunction "TVDD33_49") (pintype "power_in"))
      (node (ref "R1") (pin "2") (pinfunction "2_2") (pintype "passive"))
      (node (ref "R12") (pin "2") (pinfunction "2_2") (pintype "passive"))
      (node (ref "R14") (pin "2") (pinfunction "2_2") (pintype "passive"))
      (node (ref "R17") (pin "2") (pinfunction "2_2") (pintype "passive"))
      (node (ref "R21") (pin "2") (pinfunction "2_2") (pintype "passive"))
      (node (ref "R3") (pin "2") (pinfunction "2_2") (pintype "passive"))
      (node (ref "R4") (pin "2") (pinfunction "2_2") (pintype "passive"))
      (node (ref "R5") (pin "2") (pinfunction "2_2") (pintype "passive"))
      (node (ref "R7") (pin "2") (pinfunction "2_2") (pintype "passive"))
      (node (ref "R8") (pin "2") (pinfunction "2_2") (pintype "passive"))
    )
    (net (code "53") (name "unconnected-(IC1-FRAME1N-Pad1)") (class "Default")
      (node (ref "IC1") (pin "1") (pinfunction "FRAME1N_1") (pintype "output+no_connect"))
    )
    (net (code "54") (name "unconnected-(IC1-FRAME1P-Pad2)") (class "Default")
      (node (ref "IC1") (pin "2") (pinfunction "FRAME1P_2") (pintype "output+no_connect"))
    )
    (net (code "55") (name "unconnected-(IC1-FRAME2N-Pad5)") (class "Default")
      (node (ref "IC1") (pin "5") (pinfunction "FRAME2N_5") (pintype "output+no_connect"))
    )
    (net (code "56") (name "unconnected-(IC1-FRAME2P-Pad6)") (class "Default")
      (node (ref "IC1") (pin "6") (pinfunction "FRAME2P_6") (pintype "output+no_connect"))
    )
    (net (code "57") (name "unconnected-(IC1-FRAME3N-Pad9)") (class "Default")
      (node (ref "IC1") (pin "9") (pinfunction "FRAME3N_9") (pintype "output+no_connect"))
    )
    (net (code "58") (name "unconnected-(IC1-FRAME3P-Pad10)") (class "Default")
      (node (ref "IC1") (pin "10") (pinfunction "FRAME3P_10") (pintype "output+no_connect"))
    )
    (net (code "59") (name "unconnected-(IC1-FRAME4N-Pad13)") (class "Default")
      (node (ref "IC1") (pin "13") (pinfunction "FRAME4N_13") (pintype "output+no_connect"))
    )
    (net (code "60") (name "unconnected-(IC1-FRAME4P-Pad14)") (class "Default")
      (node (ref "IC1") (pin "14") (pinfunction "FRAME4P_14") (pintype "output+no_connect"))
    )
    (net (code "61") (name "unconnected-(IC1-LCLKOUTN-Pad17)") (class "Default")
      (node (ref "IC1") (pin "17") (pinfunction "LCLKOUTN_17") (pintype "output+no_connect"))
    )
    (net (code "62") (name "unconnected-(IC1-LCLKOUTP-Pad18)") (class "Default")
      (node (ref "IC1") (pin "18") (pinfunction "LCLKOUTP_18") (pintype "output+no_connect"))
    )
    (net (code "63") (name "unconnected-(IC1-SDO1N-Pad3)") (class "Default")
      (node (ref "IC1") (pin "3") (pinfunction "SDO1N_3") (pintype "output+no_connect"))
    )
    (net (code "64") (name "unconnected-(IC1-SDO1P-Pad4)") (class "Default")
      (node (ref "IC1") (pin "4") (pinfunction "SDO1P_4") (pintype "output+no_connect"))
    )
    (net (code "65") (name "unconnected-(IC1-SDO2N-Pad7)") (class "Default")
      (node (ref "IC1") (pin "7") (pinfunction "SDO2N_7") (pintype "output+no_connect"))
    )
    (net (code "66") (name "unconnected-(IC1-SDO2P-Pad8)") (class "Default")
      (node (ref "IC1") (pin "8") (pinfunction "SDO2P_8") (pintype "output+no_connect"))
    )
    (net (code "67") (name "unconnected-(IC1-SDO3N-Pad11)") (class "Default")
      (node (ref "IC1") (pin "11") (pinfunction "SDO3N_11") (pintype "output+no_connect"))
    )
    (net (code "68") (name "unconnected-(IC1-SDO3P-Pad12)") (class "Default")
      (node (ref "IC1") (pin "12") (pinfunction "SDO3P_12") (pintype "output+no_connect"))
    )
    (net (code "69") (name "unconnected-(IC1-SDO4N-Pad15)") (class "Default")
      (node (ref "IC1") (pin "15") (pinfunction "SDO4N_15") (pintype "output+no_connect"))
    )
    (net (code "70") (name "unconnected-(IC1-SDO4P-Pad16)") (class "Default")
      (node (ref "IC1") (pin "16") (pinfunction "SDO4P_16") (pintype "output+no_connect"))
    )
  )
)
